# Status_board_-_mode_switch_C.net
KiCad netlist of a schematic drawn in EAGLE
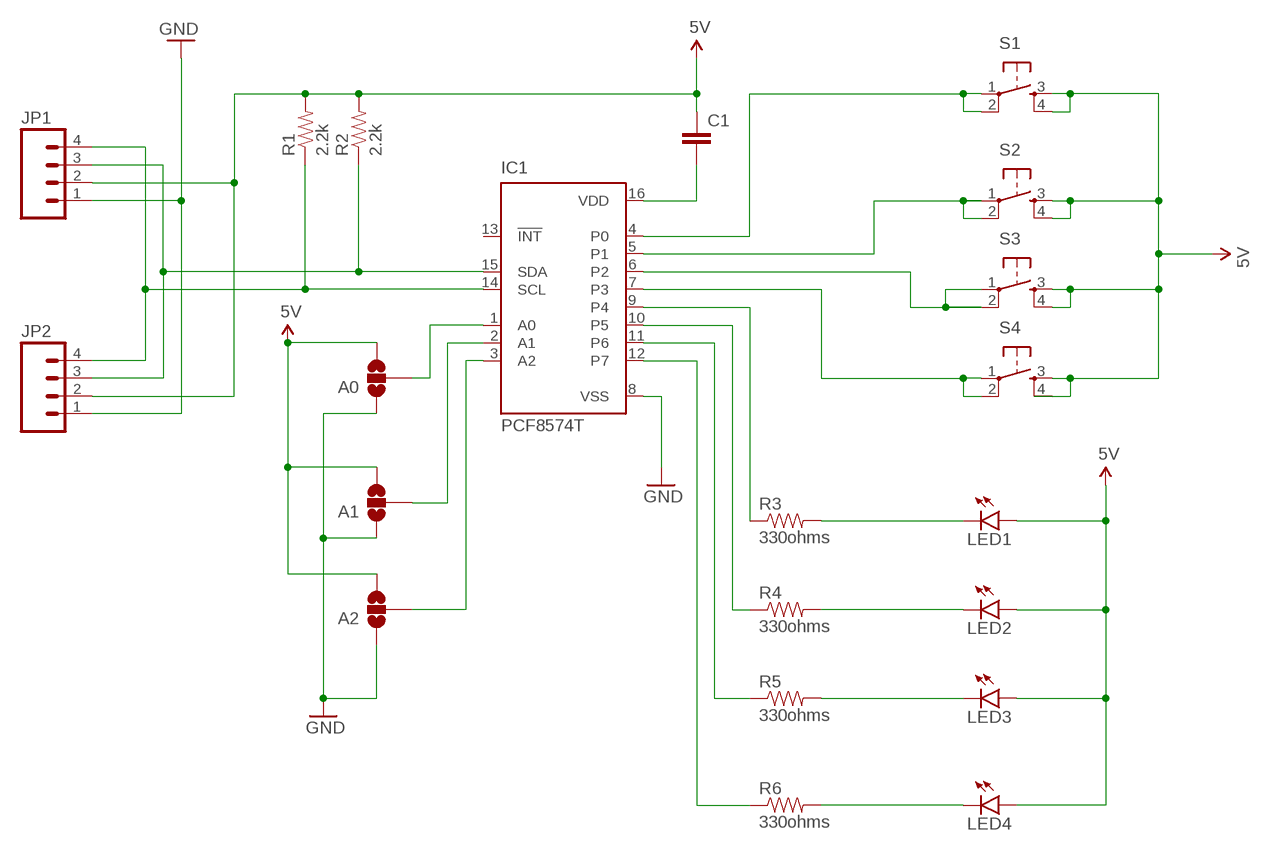
[diagram p0: schematic, sheet 1]

(export (version "E")
  (design (tool "Eeschema 10.0.6"))
  (components
    (comp (ref "A0")
      (value "SOLDERJUMPER_2WAYS")
      (footprint "eagle-import:SJ_3")
      (libsource (lib "eagle-import") (part "SOLDERJUMPER_2WAYS"))
    )
    (comp (ref "A1")
      (value "SOLDERJUMPER_2WAYS")
      (footprint "eagle-import:SJ_3")
      (libsource (lib "eagle-import") (part "SOLDERJUMPER_2WAYS"))
    )
    (comp (ref "A2")
      (value "SOLDERJUMPER_2WAYS")
      (footprint "eagle-import:SJ_3")
      (libsource (lib "eagle-import") (part "SOLDERJUMPER_2WAYS"))
    )
    (comp (ref "C1")
      (value "CAPPTH2")
      (footprint "eagle-import:CAP-PTH-SMALL2")
      (libsource (lib "eagle-import") (part "CAPPTH2"))
    )
    (comp (ref "IC1")
      (value "PCF8574T")
      (footprint "eagle-import:SO16W")
      (libsource (lib "eagle-import") (part "PCF8574T"))
    )
    (comp (ref "JP1")
      (value "M04PTH")
      (footprint "eagle-import:1X04")
      (libsource (lib "eagle-import") (part "M04PTH"))
    )
    (comp (ref "JP2")
      (value "M04PTH")
      (footprint "eagle-import:1X04")
      (libsource (lib "eagle-import") (part "M04PTH"))
    )
    (comp (ref "LED1")
      (value "LED3MM")
      (footprint "eagle-import:LED3MM")
      (libsource (lib "eagle-import") (part "LED3MM"))
    )
    (comp (ref "LED2")
      (value "LED3MM")
      (footprint "eagle-import:LED3MM")
      (libsource (lib "eagle-import") (part "LED3MM"))
    )
    (comp (ref "LED3")
      (value "LED3MM")
      (footprint "eagle-import:LED3MM")
      (libsource (lib "eagle-import") (part "LED3MM"))
    )
    (comp (ref "LED4")
      (value "LED3MM")
      (footprint "eagle-import:LED3MM")
      (libsource (lib "eagle-import") (part "LED3MM"))
    )
    (comp (ref "R1")
      (value "2.2k")
      (footprint "eagle-import:AXIAL-0.3")
      (libsource (lib "eagle-import") (part "RESISTORAXIAL-0.3"))
    )
    (comp (ref "R2")
      (value "2.2k")
      (footprint "eagle-import:AXIAL-0.3")
      (libsource (lib "eagle-import") (part "RESISTORAXIAL-0.3"))
    )
    (comp (ref "R3")
      (value "330ohms")
      (footprint "eagle-import:AXIAL-0.3")
      (libsource (lib "eagle-import") (part "RESISTORAXIAL-0.3"))
    )
    (comp (ref "R4")
      (value "330ohms")
      (footprint "eagle-import:AXIAL-0.3")
      (libsource (lib "eagle-import") (part "RESISTORAXIAL-0.3"))
    )
    (comp (ref "R5")
      (value "330ohms")
      (footprint "eagle-import:AXIAL-0.3")
      (libsource (lib "eagle-import") (part "RESISTORAXIAL-0.3"))
    )
    (comp (ref "R6")
      (value "330ohms")
      (footprint "eagle-import:AXIAL-0.3")
      (libsource (lib "eagle-import") (part "RESISTORAXIAL-0.3"))
    )
    (comp (ref "S1")
      (value "TAC_SWITCHPTH")
      (footprint "eagle-import:TACTILE-PTH")
      (libsource (lib "eagle-import") (part "TAC_SWITCHPTH"))
    )
    (comp (ref "S2")
      (value "TAC_SWITCHPTH")
      (footprint "eagle-import:TACTILE-PTH")
      (libsource (lib "eagle-import") (part "TAC_SWITCHPTH"))
    )
    (comp (ref "S3")
      (value "TAC_SWITCHPTH")
      (footprint "eagle-import:TACTILE-PTH")
      (libsource (lib "eagle-import") (part "TAC_SWITCHPTH"))
    )
    (comp (ref "S4")
      (value "TAC_SWITCHPTH")
      (footprint "eagle-import:TACTILE-PTH")
      (libsource (lib "eagle-import") (part "TAC_SWITCHPTH"))
    )
  )
  (nets
    (net (code "1") (name "5V") (class "Default")
      (node (ref "A0") (pin "3") (pinfunction "3_3") (pintype "passive"))
      (node (ref "A1") (pin "3") (pinfunction "3_3") (pintype "passive"))
      (node (ref "A2") (pin "3") (pinfunction "3_3") (pintype "passive"))
      (node (ref "C1") (pin "1") (pinfunction "1_1") (pintype "passive"))
      (node (ref "JP1") (pin "2") (pinfunction "2_2") (pintype "passive"))
      (node (ref "JP2") (pin "2") (pinfunction "2_2") (pintype "passive"))
      (node (ref "LED1") (pin "A") (pinfunction "A_A") (pintype "passive"))
      (node (ref "LED2") (pin "A") (pinfunction "A_A") (pintype "passive"))
      (node (ref "LED3") (pin "A") (pinfunction "A_A") (pintype "passive"))
      (node (ref "LED4") (pin "A") (pinfunction "A_A") (pintype "passive"))
      (node (ref "R1") (pin "P$2") (pinfunction "2_P$2") (pintype "passive"))
      (node (ref "R2") (pin "P$2") (pinfunction "2_P$2") (pintype "passive"))
      (node (ref "S1") (pin "3") (pinfunction "3_3") (pintype "passive"))
      (node (ref "S1") (pin "4") (pinfunction "4_4") (pintype "passive"))
      (node (ref "S2") (pin "3") (pinfunction "3_3") (pintype "passive"))
      (node (ref "S2") (pin "4") (pinfunction "4_4") (pintype "passive"))
      (node (ref "S3") (pin "3") (pinfunction "3_3") (pintype "passive"))
      (node (ref "S3") (pin "4") (pinfunction "4_4") (pintype "passive"))
      (node (ref "S4") (pin "3") (pinfunction "3_3") (pintype "passive"))
      (node (ref "S4") (pin "4") (pinfunction "4_4") (pintype "passive"))
    )
    (net (code "2") (name "GND") (class "Default")
      (node (ref "A0") (pin "1") (pinfunction "1_1") (pintype "passive"))
      (node (ref "A1") (pin "1") (pinfunction "1_1") (pintype "passive"))
      (node (ref "A2") (pin "1") (pinfunction "1_1") (pintype "passive"))
      (node (ref "IC1") (pin "8") (pinfunction "VSS_8") (pintype "power_in"))
      (node (ref "JP1") (pin "1") (pinfunction "1_1") (pintype "passive"))
      (node (ref "JP2") (pin "1") (pinfunction "1_1") (pintype "passive"))
    )
    (net (code "3") (name "Net-(IC1-A0)") (class "Default")
      (node (ref "A0") (pin "2") (pinfunction "2_2") (pintype "passive"))
      (node (ref "IC1") (pin "1") (pinfunction "A0_1") (pintype "input"))
    )
    (net (code "4") (name "Net-(IC1-A1)") (class "Default")
      (node (ref "A1") (pin "2") (pinfunction "2_2") (pintype "passive"))
      (node (ref "IC1") (pin "2") (pinfunction "A1_2") (pintype "input"))
    )
    (net (code "5") (name "Net-(IC1-A2)") (class "Default")
      (node (ref "A2") (pin "2") (pinfunction "2_2") (pintype "passive"))
      (node (ref "IC1") (pin "3") (pinfunction "A2_3") (pintype "input"))
    )
    (net (code "6") (name "Net-(IC1-P0)") (class "Default")
      (node (ref "IC1") (pin "4") (pinfunction "P0_4") (pintype "bidirectional"))
      (node (ref "S1") (pin "1") (pinfunction "1_1") (pintype "passive"))
      (node (ref "S1") (pin "2") (pinfunction "2_2") (pintype "passive"))
    )
    (net (code "7") (name "Net-(IC1-P1)") (class "Default")
      (node (ref "IC1") (pin "5") (pinfunction "P1_5") (pintype "bidirectional"))
      (node (ref "S2") (pin "1") (pinfunction "1_1") (pintype "passive"))
      (node (ref "S2") (pin "2") (pinfunction "2_2") (pintype "passive"))
    )
    (net (code "8") (name "Net-(IC1-P2)") (class "Default")
      (node (ref "IC1") (pin "6") (pinfunction "P2_6") (pintype "bidirectional"))
      (node (ref "S3") (pin "1") (pinfunction "1_1") (pintype "passive"))
      (node (ref "S3") (pin "2") (pinfunction "2_2") (pintype "passive"))
    )
    (net (code "9") (name "Net-(IC1-P3)") (class "Default")
      (node (ref "IC1") (pin "7") (pinfunction "P3_7") (pintype "bidirectional"))
      (node (ref "S4") (pin "1") (pinfunction "1_1") (pintype "passive"))
      (node (ref "S4") (pin "2") (pinfunction "2_2") (pintype "passive"))
    )
    (net (code "10") (name "Net-(IC1-P4)") (class "Default")
      (node (ref "IC1") (pin "9") (pinfunction "P4_9") (pintype "bidirectional"))
      (node (ref "R3") (pin "P$1") (pinfunction "1_P$1") (pintype "passive"))
    )
    (net (code "11") (name "Net-(IC1-P5)") (class "Default")
      (node (ref "IC1") (pin "10") (pinfunction "P5_10") (pintype "bidirectional"))
      (node (ref "R4") (pin "P$1") (pinfunction "1_P$1") (pintype "passive"))
    )
    (net (code "12") (name "Net-(IC1-P6)") (class "Default")
      (node (ref "IC1") (pin "11") (pinfunction "P6_11") (pintype "bidirectional"))
      (node (ref "R5") (pin "P$1") (pinfunction "1_P$1") (pintype "passive"))
    )
    (net (code "13") (name "Net-(IC1-P7)") (class "Default")
      (node (ref "IC1") (pin "12") (pinfunction "P7_12") (pintype "bidirectional"))
      (node (ref "R6") (pin "P$1") (pinfunction "1_P$1") (pintype "passive"))
    )
    (net (code "14") (name "Net-(IC1-SCL)") (class "Default")
      (node (ref "IC1") (pin "14") (pinfunction "SCL_14") (pintype "input"))
      (node (ref "JP1") (pin "4") (pinfunction "4_4") (pintype "passive"))
      (node (ref "JP2") (pin "4") (pinfunction "4_4") (pintype "passive"))
      (node (ref "R1") (pin "P$1") (pinfunction "1_P$1") (pintype "passive"))
    )
    (net (code "15") (name "Net-(IC1-SDA)") (class "Default")
      (node (ref "IC1") (pin "15") (pinfunction "SDA_15") (pintype "bidirectional"))
      (node (ref "JP1") (pin "3") (pinfunction "3_3") (pintype "passive"))
      (node (ref "JP2") (pin "3") (pinfunction "3_3") (pintype "passive"))
      (node (ref "R2") (pin "P$1") (pinfunction "1_P$1") (pintype "passive"))
    )
    (net (code "16") (name "Net-(IC1-VDD)") (class "Default")
      (node (ref "C1") (pin "2") (pinfunction "2_2") (pintype "passive"))
      (node (ref "IC1") (pin "16") (pinfunction "VDD_16") (pintype "power_in"))
    )
    (net (code "17") (name "Net-(LED1-C)") (class "Default")
      (node (ref "LED1") (pin "K") (pinfunction "C_K") (pintype "passive"))
      (node (ref "R3") (pin "P$2") (pinfunction "2_P$2") (pintype "passive"))
    )
    (net (code "18") (name "Net-(LED2-C)") (class "Default")
      (node (ref "LED2") (pin "K") (pinfunction "C_K") (pintype "passive"))
      (node (ref "R4") (pin "P$2") (pinfunction "2_P$2") (pintype "passive"))
    )
    (net (code "19") (name "Net-(LED3-C)") (class "Default")
      (node (ref "LED3") (pin "K") (pinfunction "C_K") (pintype "passive"))
      (node (ref "R5") (pin "P$2") (pinfunction "2_P$2") (pintype "passive"))
    )
    (net (code "20") (name "Net-(LED4-C)") (class "Default")
      (node (ref "LED4") (pin "K") (pinfunction "C_K") (pintype "passive"))
      (node (ref "R6") (pin "P$2") (pinfunction "2_P$2") (pintype "passive"))
    )
    (net (code "21") (name "unconnected-(IC1-~{INT}-Pad13)") (class "Default")
      (node (ref "IC1") (pin "13") (pinfunction "~{INT}_13") (pintype "output"))
    )
  )
)
